# RASPmini.net
KiCad netlist of a schematic drawn in Altium Designer
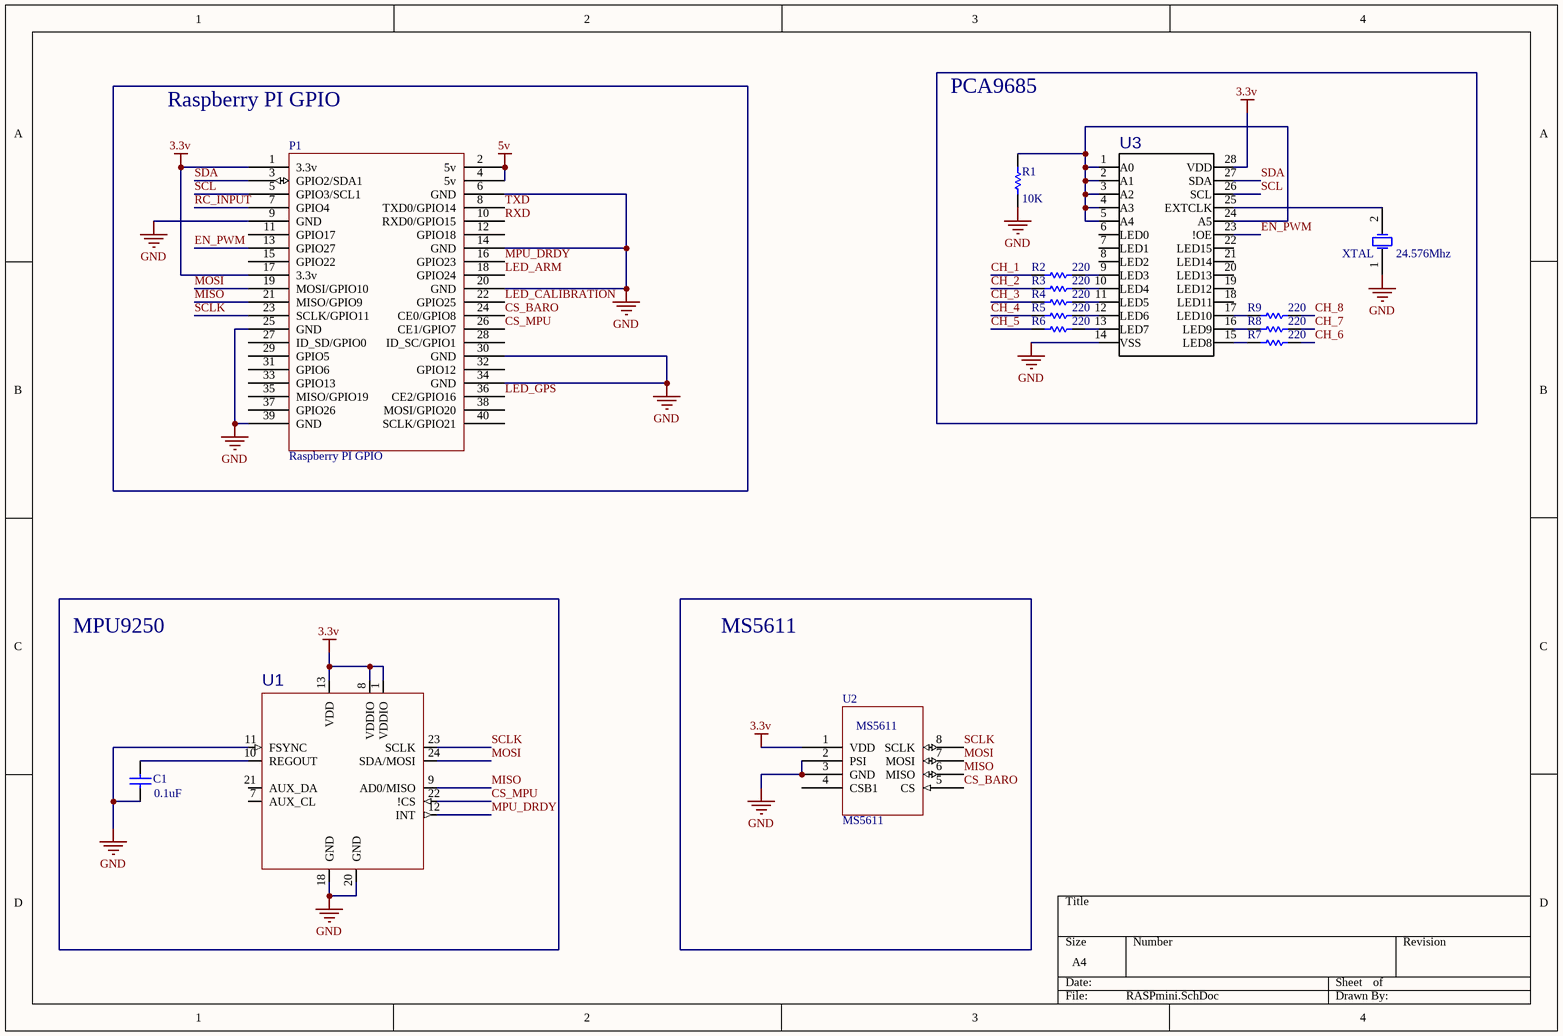
[diagram p0: RASPmini.SchDoc]

(export (version "E")
  (design (tool "Eeschema 10.0.6"))
  (components
    (comp (ref "24.576Mhz")
      (value "XTAL")
      (footprint "R38")
      (description "Crystal Oscillator")
      (fields (field (name "PUBLISHER") "Altium Limited"))
      (libsource (lib "Miscellaneous Devices") (part "XTAL"))
    )
    (comp (ref "C1")
      (value "0.1uF")
      (footprint "RAD-0.3")
      (description "Capacitor")
      (fields (field (name "Comment") "Cap") (field (name "PUBLISHER") "Altium Limited"))
      (libsource (lib "Miscellaneous Devices") (part "Cap"))
    )
    (comp (ref "P1")
      (value "Raspberry PI GPIO")
      (libsource (lib "RaspberryPI GPIO") (part "Raspberry PI GPIO"))
    )
    (comp (ref "R1")
      (value "10K")
      (footprint "AXIAL-0.3")
      (description "Resistor")
      (fields (field (name "Comment") "Res1") (field (name "PUBLISHER") "Altium Limited"))
      (libsource (lib "Miscellaneous Devices") (part "Res1"))
    )
    (comp (ref "R2")
      (value "220")
      (footprint "AXIAL-0.3")
      (description "Resistor")
      (fields (field (name "Comment") "Res1") (field (name "PUBLISHER") "Altium Limited"))
      (libsource (lib "Miscellaneous Devices") (part "Res1"))
    )
    (comp (ref "R3")
      (value "220")
      (footprint "AXIAL-0.3")
      (description "Resistor")
      (fields (field (name "Comment") "Res1") (field (name "PUBLISHER") "Altium Limited"))
      (libsource (lib "Miscellaneous Devices") (part "Res1"))
    )
    (comp (ref "R4")
      (value "220")
      (footprint "AXIAL-0.3")
      (description "Resistor")
      (fields (field (name "Comment") "Res1") (field (name "PUBLISHER") "Altium Limited"))
      (libsource (lib "Miscellaneous Devices") (part "Res1"))
    )
    (comp (ref "R5")
      (value "220")
      (footprint "AXIAL-0.3")
      (description "Resistor")
      (fields (field (name "Comment") "Res1") (field (name "PUBLISHER") "Altium Limited"))
      (libsource (lib "Miscellaneous Devices") (part "Res1"))
    )
    (comp (ref "R6")
      (value "220")
      (footprint "AXIAL-0.3")
      (description "Resistor")
      (fields (field (name "Comment") "Res1") (field (name "PUBLISHER") "Altium Limited"))
      (libsource (lib "Miscellaneous Devices") (part "Res1"))
    )
    (comp (ref "R7")
      (value "220")
      (footprint "AXIAL-0.3")
      (description "Resistor")
      (fields (field (name "Comment") "Res1") (field (name "PUBLISHER") "Altium Limited"))
      (libsource (lib "Miscellaneous Devices") (part "Res1"))
    )
    (comp (ref "R8")
      (value "220")
      (footprint "AXIAL-0.3")
      (description "Resistor")
      (fields (field (name "Comment") "Res1") (field (name "PUBLISHER") "Altium Limited"))
      (libsource (lib "Miscellaneous Devices") (part "Res1"))
    )
    (comp (ref "R9")
      (value "220")
      (footprint "AXIAL-0.3")
      (description "Resistor")
      (fields (field (name "Comment") "Res1") (field (name "PUBLISHER") "Altium Limited"))
      (libsource (lib "Miscellaneous Devices") (part "Res1"))
    )
    (comp (ref "U1")
      (value "MPU-9250")
      (footprint "QFN-24/3MM")
      (description "SMD Gyroscope/Accelerometer/Magnetometer Sensor; 9-AXIS")
      (fields (field (name "MF") "InvenSense"))
      (libsource (lib "MPU-9250") (part "MPU-9250"))
    )
    (comp (ref "U2") (value "MS5611") (libsource (lib "MS5611") (part "MS5611")))
    (comp (ref "U3")
      (value "DRIVER-PCA9685PW(TSSOP28)")
      (footprint "TSSOP28-0.65-9.7X4.4MM")
      (description "SMD IC LED DRVR, LIN DIM 25MA, 16 channels, 12bit")
      (fields (field (name "MF") "NXP Semiconductors") (field (name "MP") "PCA9685PW"))
      (libsource (lib "DRIVER-PCA9685PW_TSSOP28_") (part "DRIVER-PCA9685PW(TSSOP28)"))
    )
  )
  (nets
    (net (code "1") (name "/CH_1") (class "Default")
      (node (ref "R2") (pin "1") (pinfunction "1_1") (pintype "passive"))
    )
    (net (code "2") (name "/CH_2") (class "Default")
      (node (ref "R3") (pin "1") (pinfunction "1_1") (pintype "passive"))
    )
    (net (code "3") (name "/CH_3") (class "Default")
      (node (ref "R4") (pin "1") (pinfunction "1_1") (pintype "passive"))
    )
    (net (code "4") (name "/CH_4") (class "Default")
      (node (ref "R5") (pin "1") (pinfunction "1_1") (pintype "passive"))
    )
    (net (code "5") (name "/CH_5") (class "Default")
      (node (ref "R6") (pin "1") (pinfunction "1_1") (pintype "passive"))
    )
    (net (code "6") (name "/CH_6") (class "Default")
      (node (ref "R7") (pin "2") (pinfunction "2_2") (pintype "passive"))
    )
    (net (code "7") (name "/CH_7") (class "Default")
      (node (ref "R8") (pin "2") (pinfunction "2_2") (pintype "passive"))
    )
    (net (code "8") (name "/CH_8") (class "Default")
      (node (ref "R9") (pin "2") (pinfunction "2_2") (pintype "passive"))
    )
    (net (code "9") (name "/CS_BARO") (class "Default")
      (node (ref "P1") (pin "24") (pinfunction "CE0/GPIO8_24") (pintype "passive"))
      (node (ref "U2") (pin "5") (pinfunction "CS_5") (pintype "input"))
    )
    (net (code "10") (name "/CS_MPU") (class "Default")
      (node (ref "P1") (pin "26") (pinfunction "CE1/GPIO7_26") (pintype "passive"))
      (node (ref "U1") (pin "22") (pinfunction "!CS_22") (pintype "input"))
    )
    (net (code "11") (name "/EN_PWM") (class "Default")
      (node (ref "P1") (pin "13") (pinfunction "GPIO27_13") (pintype "passive"))
      (node (ref "U3") (pin "23") (pinfunction "!OE_23") (pintype "bidirectional"))
    )
    (net (code "12") (name "/LED_ARM") (class "Default")
      (node (ref "P1") (pin "18") (pinfunction "GPIO24_18") (pintype "passive"))
    )
    (net (code "13") (name "/LED_CALIBRATION") (class "Default")
      (node (ref "P1") (pin "22") (pinfunction "GPIO25_22") (pintype "passive"))
    )
    (net (code "14") (name "/LED_GPS") (class "Default")
      (node (ref "P1") (pin "36") (pinfunction "CE2/GPIO16_36") (pintype "passive"))
    )
    (net (code "15") (name "/MISO") (class "Default")
      (node (ref "P1") (pin "21") (pinfunction "MISO/GPIO9_21") (pintype "passive"))
      (node (ref "U1") (pin "9") (pinfunction "AD0/MISO_9") (pintype "bidirectional"))
      (node (ref "U2") (pin "6") (pinfunction "MISO_6") (pintype "bidirectional"))
    )
    (net (code "16") (name "/MOSI") (class "Default")
      (node (ref "P1") (pin "19") (pinfunction "MOSI/GPIO10_19") (pintype "passive"))
      (node (ref "U1") (pin "24") (pinfunction "SDA/MOSI_24") (pintype "bidirectional"))
      (node (ref "U2") (pin "7") (pinfunction "MOSI_7") (pintype "bidirectional"))
    )
    (net (code "17") (name "/MPU_DRDY") (class "Default")
      (node (ref "P1") (pin "16") (pinfunction "GPIO23_16") (pintype "passive"))
      (node (ref "U1") (pin "12") (pinfunction "INT_12") (pintype "output"))
    )
    (net (code "18") (name "/RC_INPUT") (class "Default")
      (node (ref "P1") (pin "7") (pinfunction "GPIO4_7") (pintype "passive"))
    )
    (net (code "19") (name "/RXD") (class "Default")
      (node (ref "P1") (pin "10") (pinfunction "RXD0/GPIO15_10") (pintype "passive"))
    )
    (net (code "20") (name "/SCL") (class "Default")
      (node (ref "P1") (pin "5") (pinfunction "GPIO3/SCL1_5") (pintype "passive"))
      (node (ref "U3") (pin "26") (pinfunction "SCL_26") (pintype "bidirectional"))
    )
    (net (code "21") (name "/SCLK") (class "Default")
      (node (ref "P1") (pin "23") (pinfunction "SCLK/GPIO11_23") (pintype "passive"))
      (node (ref "U1") (pin "23") (pinfunction "SCLK_23") (pintype "bidirectional"))
      (node (ref "U2") (pin "8") (pinfunction "SCLK_8") (pintype "bidirectional"))
    )
    (net (code "22") (name "/SDA") (class "Default")
      (node (ref "P1") (pin "3") (pinfunction "GPIO2/SDA1_3") (pintype "bidirectional"))
      (node (ref "U3") (pin "27") (pinfunction "SDA_27") (pintype "bidirectional"))
    )
    (net (code "23") (name "/TXD") (class "Default")
      (node (ref "P1") (pin "8") (pinfunction "TXD0/GPIO14_8") (pintype "passive"))
    )
    (net (code "24") (name "3.3v") (class "Default")
      (node (ref "P1") (pin "1") (pinfunction "3.3v_1") (pintype "power_in"))
      (node (ref "P1") (pin "17") (pinfunction "3.3v_17") (pintype "passive"))
      (node (ref "U1") (pin "1") (pinfunction "VDDIO_1") (pintype "power_in"))
      (node (ref "U1") (pin "13") (pinfunction "VDD_13") (pintype "power_in"))
      (node (ref "U1") (pin "8") (pinfunction "VDDIO_8") (pintype "power_in"))
      (node (ref "U2") (pin "1") (pinfunction "VDD_1") (pintype "power_in"))
      (node (ref "U3") (pin "28") (pinfunction "VDD_28") (pintype "bidirectional"))
    )
    (net (code "25") (name "5v") (class "Default")
      (node (ref "P1") (pin "2") (pinfunction "5v_2") (pintype "power_in"))
      (node (ref "P1") (pin "4") (pinfunction "5v_4") (pintype "power_in"))
    )
    (net (code "26") (name "GND") (class "Default")
      (node (ref "24.576Mhz") (pin "1") (pinfunction "OSC1_1") (pintype "passive"))
      (node (ref "C1") (pin "1") (pinfunction "1_1") (pintype "passive"))
      (node (ref "P1") (pin "14") (pinfunction "GND_14") (pintype "passive"))
      (node (ref "P1") (pin "20") (pinfunction "GND_20") (pintype "passive"))
      (node (ref "P1") (pin "25") (pinfunction "GND_25") (pintype "passive"))
      (node (ref "P1") (pin "30") (pinfunction "GND_30") (pintype "passive"))
      (node (ref "P1") (pin "34") (pinfunction "GND_34") (pintype "passive"))
      (node (ref "P1") (pin "39") (pinfunction "GND_39") (pintype "passive"))
      (node (ref "P1") (pin "6") (pinfunction "GND_6") (pintype "passive"))
      (node (ref "P1") (pin "9") (pinfunction "GND_9") (pintype "passive"))
      (node (ref "R1") (pin "1") (pinfunction "1_1") (pintype "passive"))
      (node (ref "U1") (pin "11") (pinfunction "FSYNC_11") (pintype "input"))
      (node (ref "U1") (pin "18") (pinfunction "GND_18") (pintype "power_in"))
      (node (ref "U1") (pin "20") (pinfunction "GND_20") (pintype "power_in"))
      (node (ref "U2") (pin "2") (pinfunction "PSI_2") (pintype "passive"))
      (node (ref "U2") (pin "3") (pinfunction "GND_3") (pintype "passive"))
      (node (ref "U3") (pin "14") (pinfunction "VSS_14") (pintype "bidirectional"))
    )
    (net (code "27") (name "Net-(24.576Mhz-OSC2)") (class "Default")
      (node (ref "24.576Mhz") (pin "2") (pinfunction "OSC2_2") (pintype "passive"))
      (node (ref "U3") (pin "25") (pinfunction "EXTCLK_25") (pintype "bidirectional"))
    )
    (net (code "28") (name "Net-(U1-REGOUT)") (class "Default")
      (node (ref "C1") (pin "2") (pinfunction "2_2") (pintype "passive"))
      (node (ref "U1") (pin "10") (pinfunction "REGOUT_10") (pintype "bidirectional"))
    )
    (net (code "29") (name "Net-(U3-A0)") (class "Default")
      (node (ref "R1") (pin "2") (pinfunction "2_2") (pintype "passive"))
      (node (ref "U3") (pin "1") (pinfunction "A0_1") (pintype "bidirectional"))
      (node (ref "U3") (pin "2") (pinfunction "A1_2") (pintype "bidirectional"))
      (node (ref "U3") (pin "24") (pinfunction "A5_24") (pintype "bidirectional"))
      (node (ref "U3") (pin "3") (pinfunction "A2_3") (pintype "bidirectional"))
      (node (ref "U3") (pin "4") (pinfunction "A3_4") (pintype "bidirectional"))
      (node (ref "U3") (pin "5") (pinfunction "A4_5") (pintype "bidirectional"))
    )
    (net (code "30") (name "Net-(U3-LED3)") (class "Default")
      (node (ref "R2") (pin "2") (pinfunction "2_2") (pintype "passive"))
      (node (ref "U3") (pin "9") (pinfunction "LED3_9") (pintype "bidirectional"))
    )
    (net (code "31") (name "Net-(U3-LED4)") (class "Default")
      (node (ref "R3") (pin "2") (pinfunction "2_2") (pintype "passive"))
      (node (ref "U3") (pin "10") (pinfunction "LED4_10") (pintype "bidirectional"))
    )
    (net (code "32") (name "Net-(U3-LED5)") (class "Default")
      (node (ref "R4") (pin "2") (pinfunction "2_2") (pintype "passive"))
      (node (ref "U3") (pin "11") (pinfunction "LED5_11") (pintype "bidirectional"))
    )
    (net (code "33") (name "Net-(U3-LED6)") (class "Default")
      (node (ref "R5") (pin "2") (pinfunction "2_2") (pintype "passive"))
      (node (ref "U3") (pin "12") (pinfunction "LED6_12") (pintype "bidirectional"))
    )
    (net (code "34") (name "Net-(U3-LED7)") (class "Default")
      (node (ref "R6") (pin "2") (pinfunction "2_2") (pintype "passive"))
      (node (ref "U3") (pin "13") (pinfunction "LED7_13") (pintype "bidirectional"))
    )
    (net (code "35") (name "Net-(U3-LED8)") (class "Default")
      (node (ref "R7") (pin "1") (pinfunction "1_1") (pintype "passive"))
      (node (ref "U3") (pin "15") (pinfunction "LED8_15") (pintype "bidirectional"))
    )
    (net (code "36") (name "Net-(U3-LED9)") (class "Default")
      (node (ref "R8") (pin "1") (pinfunction "1_1") (pintype "passive"))
      (node (ref "U3") (pin "16") (pinfunction "LED9_16") (pintype "bidirectional"))
    )
    (net (code "37") (name "Net-(U3-LED10)") (class "Default")
      (node (ref "R9") (pin "1") (pinfunction "1_1") (pintype "passive"))
      (node (ref "U3") (pin "17") (pinfunction "LED10_17") (pintype "bidirectional"))
    )
    (net (code "38") (name "unconnected-(P1-GPIO5-Pad29)") (class "Default")
      (node (ref "P1") (pin "29") (pinfunction "GPIO5_29") (pintype "passive"))
    )
    (net (code "39") (name "unconnected-(P1-GPIO6-Pad31)") (class "Default")
      (node (ref "P1") (pin "31") (pinfunction "GPIO6_31") (pintype "passive"))
    )
    (net (code "40") (name "unconnected-(P1-GPIO12-Pad32)") (class "Default")
      (node (ref "P1") (pin "32") (pinfunction "GPIO12_32") (pintype "passive"))
    )
    (net (code "41") (name "unconnected-(P1-GPIO13-Pad33)") (class "Default")
      (node (ref "P1") (pin "33") (pinfunction "GPIO13_33") (pintype "passive"))
    )
    (net (code "42") (name "unconnected-(P1-GPIO17-Pad11)") (class "Default")
      (node (ref "P1") (pin "11") (pinfunction "GPIO17_11") (pintype "passive"))
    )
    (net (code "43") (name "unconnected-(P1-GPIO18-Pad12)") (class "Default")
      (node (ref "P1") (pin "12") (pinfunction "GPIO18_12") (pintype "passive"))
    )
    (net (code "44") (name "unconnected-(P1-GPIO22-Pad15)") (class "Default")
      (node (ref "P1") (pin "15") (pinfunction "GPIO22_15") (pintype "passive"))
    )
    (net (code "45") (name "unconnected-(P1-GPIO26-Pad37)") (class "Default")
      (node (ref "P1") (pin "37") (pinfunction "GPIO26_37") (pintype "passive"))
    )
    (net (code "46") (name "unconnected-(P1-ID_SC{slash}GPIO1-Pad28)") (class "Default")
      (node (ref "P1") (pin "28") (pinfunction "ID_SC/GPIO1_28") (pintype "passive"))
    )
    (net (code "47") (name "unconnected-(P1-ID_SD{slash}GPIO0-Pad27)") (class "Default")
      (node (ref "P1") (pin "27") (pinfunction "ID_SD/GPIO0_27") (pintype "passive"))
    )
    (net (code "48") (name "unconnected-(P1-MISO{slash}GPIO19-Pad35)") (class "Default")
      (node (ref "P1") (pin "35") (pinfunction "MISO/GPIO19_35") (pintype "passive"))
    )
    (net (code "49") (name "unconnected-(P1-MOSI{slash}GPIO20-Pad38)") (class "Default")
      (node (ref "P1") (pin "38") (pinfunction "MOSI/GPIO20_38") (pintype "passive"))
    )
    (net (code "50") (name "unconnected-(P1-SCLK{slash}GPIO21-Pad40)") (class "Default")
      (node (ref "P1") (pin "40") (pinfunction "SCLK/GPIO21_40") (pintype "passive"))
    )
    (net (code "51") (name "unconnected-(U1-AUX_CL-Pad7)") (class "Default")
      (node (ref "U1") (pin "7") (pinfunction "AUX_CL_7") (pintype "bidirectional"))
    )
    (net (code "52") (name "unconnected-(U1-AUX_DA-Pad21)") (class "Default")
      (node (ref "U1") (pin "21") (pinfunction "AUX_DA_21") (pintype "bidirectional"))
    )
    (net (code "53") (name "unconnected-(U2-CSB1-Pad4)") (class "Default")
      (node (ref "U2") (pin "4") (pinfunction "CSB1_4") (pintype "passive"))
    )
    (net (code "54") (name "unconnected-(U3-LED0-Pad6)") (class "Default")
      (node (ref "U3") (pin "6") (pinfunction "LED0_6") (pintype "bidirectional"))
    )
    (net (code "55") (name "unconnected-(U3-LED1-Pad7)") (class "Default")
      (node (ref "U3") (pin "7") (pinfunction "LED1_7") (pintype "bidirectional"))
    )
    (net (code "56") (name "unconnected-(U3-LED2-Pad8)") (class "Default")
      (node (ref "U3") (pin "8") (pinfunction "LED2_8") (pintype "bidirectional"))
    )
    (net (code "57") (name "unconnected-(U3-LED11-Pad18)") (class "Default")
      (node (ref "U3") (pin "18") (pinfunction "LED11_18") (pintype "bidirectional"))
    )
    (net (code "58") (name "unconnected-(U3-LED12-Pad19)") (class "Default")
      (node (ref "U3") (pin "19") (pinfunction "LED12_19") (pintype "bidirectional"))
    )
    (net (code "59") (name "unconnected-(U3-LED13-Pad20)") (class "Default")
      (node (ref "U3") (pin "20") (pinfunction "LED13_20") (pintype "bidirectional"))
    )
    (net (code "60") (name "unconnected-(U3-LED14-Pad21)") (class "Default")
      (node (ref "U3") (pin "21") (pinfunction "LED14_21") (pintype "bidirectional"))
    )
    (net (code "61") (name "unconnected-(U3-LED15-Pad22)") (class "Default")
      (node (ref "U3") (pin "22") (pinfunction "LED15_22") (pintype "bidirectional"))
    )
  )
)
